# 16-Power.net
KiCad netlist of a schematic drawn in Altium Designer
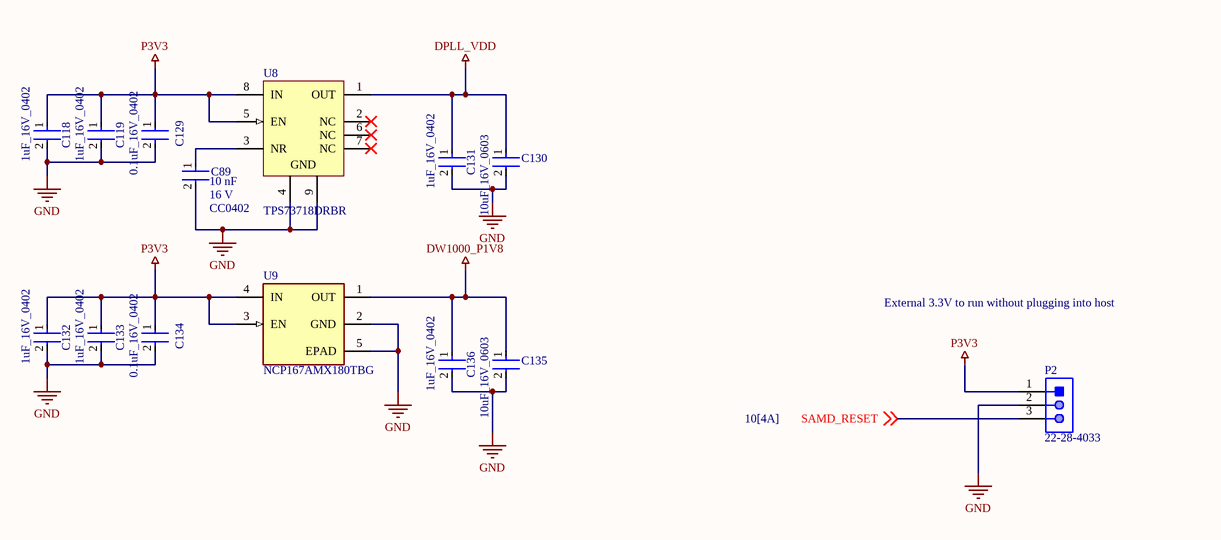
[diagram p0: 16-Power.SchDoc]

(export (version "E")
  (design (tool "Eeschema 10.0.6"))
  (components
    (comp (ref "C89")
      (value "10 nF")
      (footprint "FP-CC0402-MFG")
      (description "CAP CER 10000PF 16V X7R 0402")
      (fields
        (field (name "MANUFACTURER PART NUMBER") "CC0402KRX7R7BB103")
        (field (name "TOLERANCE") "0.1")
        (field (name "PACKAGE") "CC0402")
        (field (name "VOLTAGE RATING") "16 V")
      )
      (libsource (lib "Altium Content Vault") (part "11868f565c42a9108669ba33697ecf6"))
    )
    (comp (ref "C118")
      (value "1uF_16V_0402")
      (footprint "FP-0402-L_1_0_0_05-W_0_5-IPC_C")
      (description "None")
      (fields (field (name "TOLERANCE") "20%") (field (name "VOLTAGE") "16V"))
      (libsource (lib "Altium Content Vault") (part "b4654b650e69147ec39a6b967a45e02"))
    )
    (comp (ref "C119")
      (value "1uF_16V_0402")
      (footprint "FP-0402-L_1_0_0_05-W_0_5-IPC_C")
      (description "None")
      (fields (field (name "TOLERANCE") "20%") (field (name "VOLTAGE") "16V"))
      (libsource (lib "Altium Content Vault") (part "b4654b650e69147ec39a6b967a45e02"))
    )
    (comp (ref "C129")
      (value "0.1uF_16V_0402")
      (footprint "FP-GRM15-MFG")
      (description "CAP CER 0.1UF 16V X7R 0402")
      (fields (field (name "MANUFACTURER PART NUMBER") "GRM155R71C104KA88D") (field (name "TOLERANCE") "10%"))
      (libsource (lib "Altium Content Vault") (part "236180d848d6139a670b325ea6854c9"))
    )
    (comp (ref "C130")
      (value "10uF_16V_0603")
      (footprint "FP-MK107BA-IPC_A")
      (description "None")
      (fields (field (name "TOLERANCE") "20%"))
      (libsource (lib "Altium Content Vault") (part "b4654b650e69147ec39a6b967a45e02"))
    )
    (comp (ref "C131")
      (value "1uF_16V_0402")
      (footprint "FP-0402-L_1_0_0_05-W_0_5-IPC_C")
      (description "None")
      (fields (field (name "TOLERANCE") "20%") (field (name "VOLTAGE") "16V"))
      (libsource (lib "Altium Content Vault") (part "b4654b650e69147ec39a6b967a45e02"))
    )
    (comp (ref "C132")
      (value "1uF_16V_0402")
      (footprint "FP-0402-L_1_0_0_05-W_0_5-IPC_C")
      (description "None")
      (fields (field (name "TOLERANCE") "20%") (field (name "VOLTAGE") "16V"))
      (libsource (lib "Altium Content Vault") (part "b4654b650e69147ec39a6b967a45e02"))
    )
    (comp (ref "C133")
      (value "1uF_16V_0402")
      (footprint "FP-0402-L_1_0_0_05-W_0_5-IPC_C")
      (description "None")
      (fields (field (name "TOLERANCE") "20%") (field (name "VOLTAGE") "16V"))
      (libsource (lib "Altium Content Vault") (part "b4654b650e69147ec39a6b967a45e02"))
    )
    (comp (ref "C134")
      (value "0.1uF_16V_0402")
      (footprint "FP-GRM15-MFG")
      (description "CAP CER 0.1UF 16V X7R 0402")
      (fields (field (name "MANUFACTURER PART NUMBER") "GRM155R71C104KA88D") (field (name "TOLERANCE") "10%"))
      (libsource (lib "Altium Content Vault") (part "236180d848d6139a670b325ea6854c9"))
    )
    (comp (ref "C135")
      (value "10uF_16V_0603")
      (footprint "FP-MK107BA-IPC_A")
      (description "None")
      (fields (field (name "TOLERANCE") "20%"))
      (libsource (lib "Altium Content Vault") (part "b4654b650e69147ec39a6b967a45e02"))
    )
    (comp (ref "C136")
      (value "1uF_16V_0402")
      (footprint "FP-0402-L_1_0_0_05-W_0_5-IPC_C")
      (description "None")
      (fields (field (name "TOLERANCE") "20%") (field (name "VOLTAGE") "16V"))
      (libsource (lib "Altium Content Vault") (part "b4654b650e69147ec39a6b967a45e02"))
    )
    (comp (ref "P2")
      (value "22-28-4033")
      (footprint "MOLX-22-28-4033_V")
      (description "Male Header, Pitch 2.54 mm, 1 x 3 Position, Height 8.38 mm, Tail Length 3.18 mm, RoHS, Bulk")
      (fields (field (name "MANUFACTURER") "Molex"))
      (libsource (lib "Altium Content Vault") (part "CN-1P-M-R3"))
    )
    (comp (ref "U8")
      (value "TPS73718DRBR")
      (footprint "DRB0008A_V")
      (fields (field (name "MANUFACTURER") "Texas Instruments"))
      (libsource (lib "Altium Content Vault") (part "TI-TPS73718DRB8-1750X1500TP"))
    )
    (comp (ref "U9")
      (value "NCP167AMX180TBG")
      (footprint "FP-711AJ-MFG")
      (description "LDO 700 MA ULTRA-LOW NOI")
      (fields
        (field (name "OCTOPART") "https://octopart.com/ncp167amx330tbg-on+semiconductor-85869721")
        (field (name "MANUFACTURER") "ON Semiconductor")
      )
      (libsource (lib "Altium Content Vault") (part "8b0df6fa3425eee82d30c7ddf45be47"))
    )
  )
  (nets
    (net (code "1") (name "DPLL_VDD") (class "Default")
      (node (ref "C130") (pin "1") (pinfunction "1_1") (pintype "passive"))
      (node (ref "C131") (pin "1") (pinfunction "1_1") (pintype "passive"))
      (node (ref "U8") (pin "1") (pinfunction "OUT_1") (pintype "power_in"))
    )
    (net (code "2") (name "DW1000_P1V8") (class "Default")
      (node (ref "C135") (pin "1") (pinfunction "1_1") (pintype "passive"))
      (node (ref "C136") (pin "1") (pinfunction "1_1") (pintype "passive"))
      (node (ref "U9") (pin "1") (pinfunction "OUT_1") (pintype "power_in"))
    )
    (net (code "3") (name "GND") (class "Default")
      (node (ref "C118") (pin "2") (pinfunction "2_2") (pintype "passive"))
      (node (ref "C119") (pin "2") (pinfunction "2_2") (pintype "passive"))
      (node (ref "C129") (pin "2") (pinfunction "2_2") (pintype "passive"))
      (node (ref "C130") (pin "2") (pinfunction "2_2") (pintype "passive"))
      (node (ref "C131") (pin "2") (pinfunction "2_2") (pintype "passive"))
      (node (ref "C132") (pin "2") (pinfunction "2_2") (pintype "passive"))
      (node (ref "C133") (pin "2") (pinfunction "2_2") (pintype "passive"))
      (node (ref "C134") (pin "2") (pinfunction "2_2") (pintype "passive"))
      (node (ref "C135") (pin "2") (pinfunction "2_2") (pintype "passive"))
      (node (ref "C136") (pin "2") (pinfunction "2_2") (pintype "passive"))
      (node (ref "C89") (pin "2") (pinfunction "2_2") (pintype "passive"))
      (node (ref "P2") (pin "2") (pinfunction "2_2") (pintype "passive"))
      (node (ref "U8") (pin "4") (pinfunction "GND_4") (pintype "power_in"))
      (node (ref "U8") (pin "9") (pinfunction "GND_9") (pintype "power_in"))
      (node (ref "U9") (pin "2") (pinfunction "GND_2") (pintype "power_in"))
      (node (ref "U9") (pin "5") (pinfunction "EPAD_5") (pintype "power_in"))
    )
    (net (code "4") (name "Net-(U8-NR)") (class "Default")
      (node (ref "C89") (pin "1") (pinfunction "1_1") (pintype "passive"))
      (node (ref "U8") (pin "3") (pinfunction "NR_3") (pintype "passive"))
    )
    (net (code "5") (name "P3V3") (class "Default")
      (node (ref "C118") (pin "1") (pinfunction "1_1") (pintype "passive"))
      (node (ref "C119") (pin "1") (pinfunction "1_1") (pintype "passive"))
      (node (ref "C129") (pin "1") (pinfunction "1_1") (pintype "passive"))
      (node (ref "C132") (pin "1") (pinfunction "1_1") (pintype "passive"))
      (node (ref "C133") (pin "1") (pinfunction "1_1") (pintype "passive"))
      (node (ref "C134") (pin "1") (pinfunction "1_1") (pintype "passive"))
      (node (ref "P2") (pin "1") (pinfunction "1_1") (pintype "passive"))
      (node (ref "U8") (pin "5") (pinfunction "EN_5") (pintype "input"))
      (node (ref "U8") (pin "8") (pinfunction "IN_8") (pintype "power_in"))
      (node (ref "U9") (pin "3") (pinfunction "EN_3") (pintype "input"))
      (node (ref "U9") (pin "4") (pinfunction "IN_4") (pintype "power_in"))
    )
    (net (code "6") (name "SAMD_RESET") (class "Default")
      (node (ref "P2") (pin "3") (pinfunction "3_3") (pintype "passive"))
    )
    (net (code "7") (name "unconnected-(U8-NC-Pad2)") (class "Default")
      (node (ref "U8") (pin "2") (pinfunction "NC_2") (pintype "passive+no_connect"))
    )
    (net (code "8") (name "unconnected-(U8-NC-Pad6)") (class "Default")
      (node (ref "U8") (pin "6") (pinfunction "NC_6") (pintype "passive+no_connect"))
    )
    (net (code "9") (name "unconnected-(U8-NC-Pad7)") (class "Default")
      (node (ref "U8") (pin "7") (pinfunction "NC_7") (pintype "passive+no_connect"))
    )
  )
)
